# Power_suply.net
KiCad netlist of a schematic drawn in Altium Designer
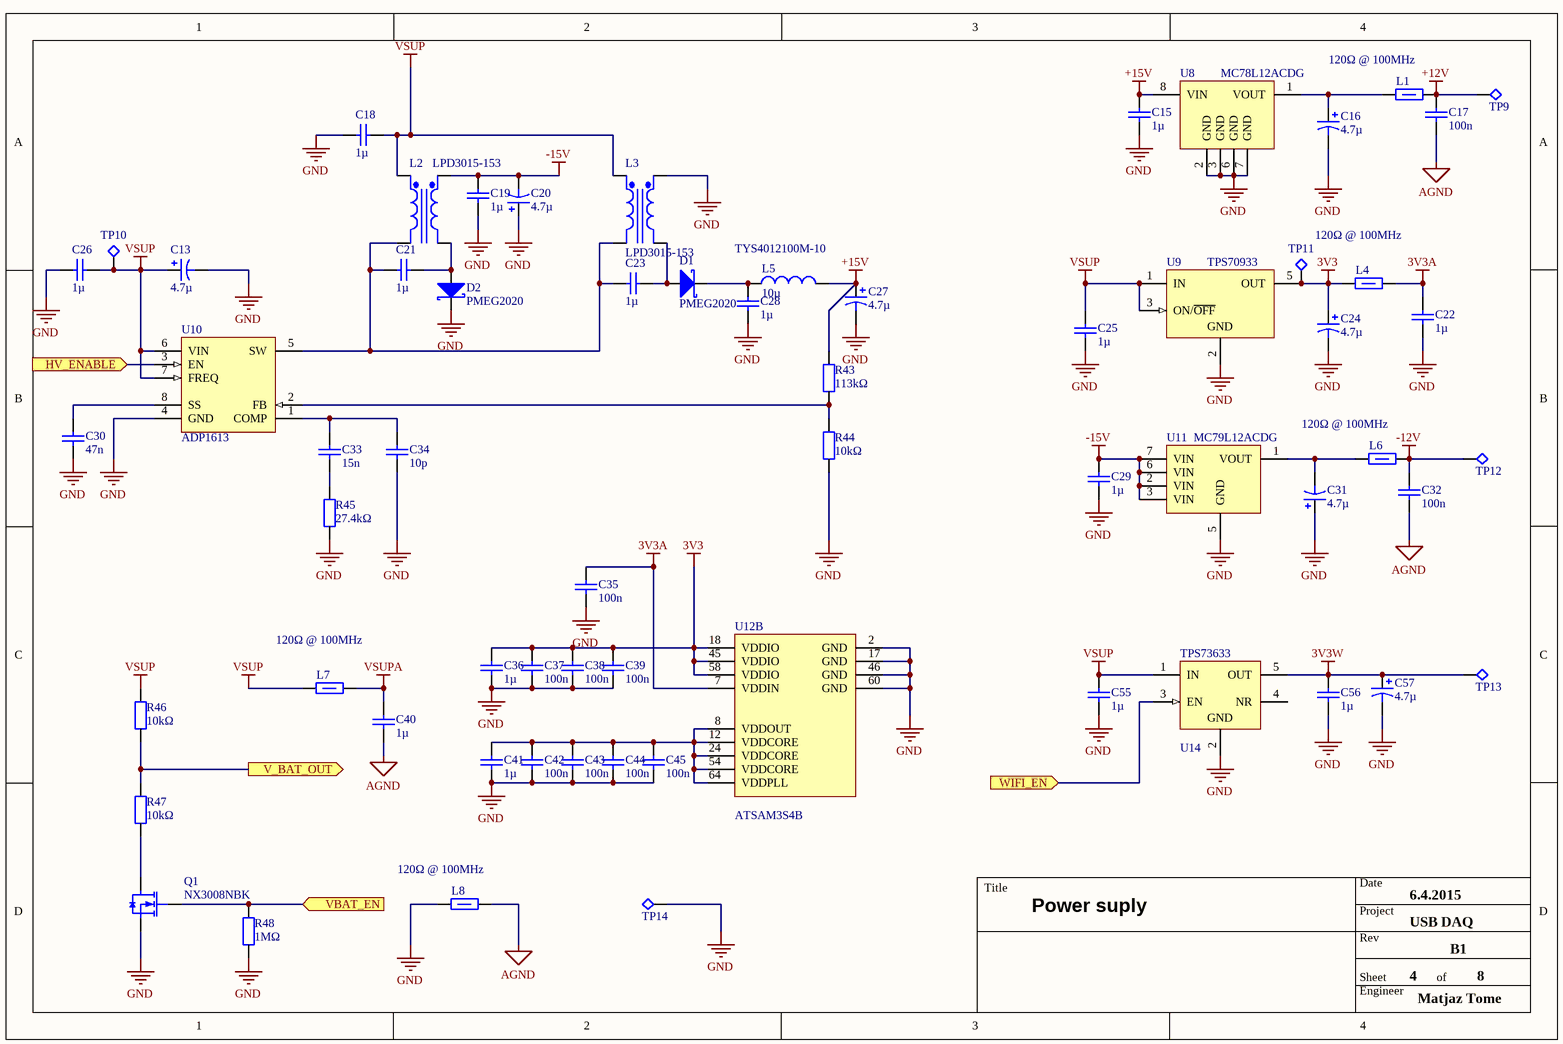
[diagram p0: Power_suply.SchDoc]

(export (version "E")
  (design (tool "Eeschema 10.0.6"))
  (components
    (comp (ref "C13")
      (value "4.7µ")
      (footprint "A")
      (description "tantalum SMD capacitor 4.7µF 16V A case")
      (fields (field (name "PART NUMBER") "CST0011") (field (name "MANUFACTURER") "Kemet"))
      (libsource (lib "components") (part "Capacitor polarized"))
    )
    (comp (ref "C15")
      (value "1µ")
      (footprint "0603C")
      (description "ceramic X5R SMD capacitor smd 0603 1µF 50V")
      (fields (field (name "PART NUMBER") "ZSC0003") (field (name "MANUFACTURER") "Murata"))
      (libsource (lib "components") (part "Capacitor"))
    )
    (comp (ref "C16")
      (value "4.7µ")
      (footprint "A")
      (description "tantalum SMD capacitor 4.7µF 16V A case")
      (fields (field (name "PART NUMBER") "CST0011") (field (name "MANUFACTURER") "Kemet"))
      (libsource (lib "components") (part "Capacitor polarized"))
    )
    (comp (ref "C17")
      (value "100n")
      (footprint "0603C")
      (description "ceramic X7R SMD capacitor smd 0603 100nF 16V")
      (fields (field (name "PART NUMBER") "RSC0013") (field (name "MANUFACTURER") "Murata"))
      (libsource (lib "components") (part "Capacitor"))
    )
    (comp (ref "C18")
      (value "1µ")
      (footprint "0603C")
      (description "ceramic X5R SMD capacitor smd 0603 1µF 50V")
      (fields (field (name "PART NUMBER") "ZSC0003") (field (name "MANUFACTURER") "Murata"))
      (libsource (lib "components") (part "Capacitor"))
    )
    (comp (ref "C19")
      (value "1µ")
      (footprint "0603C")
      (description "ceramic X5R SMD capacitor smd 0603 1µF 50V")
      (fields (field (name "PART NUMBER") "ZSC0003") (field (name "MANUFACTURER") "Murata"))
      (libsource (lib "components") (part "Capacitor"))
    )
    (comp (ref "C20")
      (value "4.7µ")
      (footprint "A")
      (description "tantalum SMD capacitor 4.7µF 16V A case")
      (fields (field (name "PART NUMBER") "CST0011") (field (name "MANUFACTURER") "Kemet"))
      (libsource (lib "components") (part "Capacitor polarized"))
    )
    (comp (ref "C21")
      (value "1µ")
      (footprint "0603C")
      (description "ceramic X5R SMD capacitor smd 0603 1µF 50V")
      (fields (field (name "PART NUMBER") "ZSC0003") (field (name "MANUFACTURER") "Murata"))
      (libsource (lib "components") (part "Capacitor"))
    )
    (comp (ref "C22")
      (value "1µ")
      (footprint "0603C")
      (description "ceramic X5R SMD capacitor smd 0603 1µF 50V")
      (fields (field (name "PART NUMBER") "ZSC0003") (field (name "MANUFACTURER") "Murata"))
      (libsource (lib "components") (part "Capacitor"))
    )
    (comp (ref "C23")
      (value "1µ")
      (footprint "0603C")
      (description "ceramic X5R SMD capacitor smd 0603 1µF 50V")
      (fields (field (name "PART NUMBER") "ZSC0003") (field (name "MANUFACTURER") "Murata"))
      (libsource (lib "components") (part "Capacitor"))
    )
    (comp (ref "C24")
      (value "4.7µ")
      (footprint "A")
      (description "tantalum SMD capacitor 4.7µF 16V A case")
      (fields (field (name "PART NUMBER") "CST0011") (field (name "MANUFACTURER") "Kemet"))
      (libsource (lib "components") (part "Capacitor polarized"))
    )
    (comp (ref "C25")
      (value "1µ")
      (footprint "0603C")
      (description "ceramic X5R SMD capacitor smd 0603 1µF 50V")
      (fields (field (name "PART NUMBER") "ZSC0003") (field (name "MANUFACTURER") "Murata"))
      (libsource (lib "components") (part "Capacitor"))
    )
    (comp (ref "C26")
      (value "1µ")
      (footprint "0603C")
      (description "ceramic X5R SMD capacitor smd 0603 1µF 50V")
      (fields (field (name "PART NUMBER") "ZSC0003") (field (name "MANUFACTURER") "Murata"))
      (libsource (lib "components") (part "Capacitor"))
    )
    (comp (ref "C27")
      (value "4.7µ")
      (footprint "A")
      (description "tantalum SMD capacitor 4.7µF 16V A case")
      (fields (field (name "PART NUMBER") "CST0011") (field (name "MANUFACTURER") "Kemet"))
      (libsource (lib "components") (part "Capacitor polarized"))
    )
    (comp (ref "C28")
      (value "1µ")
      (footprint "0603C")
      (description "ceramic X5R SMD capacitor smd 0603 1µF 50V")
      (fields (field (name "PART NUMBER") "ZSC0003") (field (name "MANUFACTURER") "Murata"))
      (libsource (lib "components") (part "Capacitor"))
    )
    (comp (ref "C29")
      (value "1µ")
      (footprint "0603C")
      (description "ceramic X5R SMD capacitor smd 0603 1µF 50V")
      (fields (field (name "PART NUMBER") "ZSC0003") (field (name "MANUFACTURER") "Murata"))
      (libsource (lib "components") (part "Capacitor"))
    )
    (comp (ref "C30")
      (value "47n")
      (footprint "0603C")
      (description "ceramic X7R SMD capacitor smd 0603 47nF 16V")
      (fields (field (name "PART NUMBER") "RSC0007") (field (name "MANUFACTURER") "Multicomp"))
      (libsource (lib "components") (part "Capacitor"))
    )
    (comp (ref "C31")
      (value "4.7µ")
      (footprint "A")
      (description "tantalum SMD capacitor 4.7µF 16V A case")
      (fields (field (name "PART NUMBER") "CST0011") (field (name "MANUFACTURER") "Kemet"))
      (libsource (lib "components") (part "Capacitor polarized"))
    )
    (comp (ref "C32")
      (value "100n")
      (footprint "0603C")
      (description "ceramic X7R SMD capacitor smd 0603 100nF 16V")
      (fields (field (name "PART NUMBER") "RSC0013") (field (name "MANUFACTURER") "Murata"))
      (libsource (lib "components") (part "Capacitor"))
    )
    (comp (ref "C33")
      (value "15n")
      (footprint "0603C")
      (description "ceramic X7R SMD capacitor smd 0603 15nF 100V")
      (fields (field (name "PART NUMBER") "RSC0015") (field (name "MANUFACTURER") "Kemet"))
      (libsource (lib "components") (part "Capacitor"))
    )
    (comp (ref "C34")
      (value "10p")
      (footprint "0603C")
      (description "ceramic C0G SMD capacitor smd 0603 10pF 100V")
      (fields (field (name "PART NUMBER") "GSC0019") (field (name "MANUFACTURER") "Kemet"))
      (libsource (lib "components") (part "Capacitor"))
    )
    (comp (ref "C35")
      (value "100n")
      (footprint "0603C")
      (description "ceramic X7R SMD capacitor smd 0603 100nF 16V")
      (fields (field (name "PART NUMBER") "RSC0013") (field (name "MANUFACTURER") "Murata"))
      (libsource (lib "components") (part "Capacitor"))
    )
    (comp (ref "C36")
      (value "1µ")
      (footprint "0603C")
      (description "ceramic X5R SMD capacitor smd 0603 1µF 50V")
      (fields (field (name "PART NUMBER") "ZSC0003") (field (name "MANUFACTURER") "Murata"))
      (libsource (lib "components") (part "Capacitor"))
    )
    (comp (ref "C37")
      (value "100n")
      (footprint "0603C")
      (description "ceramic X7R SMD capacitor smd 0603 100nF 16V")
      (fields (field (name "PART NUMBER") "RSC0013") (field (name "MANUFACTURER") "Murata"))
      (libsource (lib "components") (part "Capacitor"))
    )
    (comp (ref "C38")
      (value "100n")
      (footprint "0603C")
      (description "ceramic X7R SMD capacitor smd 0603 100nF 16V")
      (fields (field (name "PART NUMBER") "RSC0013") (field (name "MANUFACTURER") "Murata"))
      (libsource (lib "components") (part "Capacitor"))
    )
    (comp (ref "C39")
      (value "100n")
      (footprint "0603C")
      (description "ceramic X7R SMD capacitor smd 0603 100nF 16V")
      (fields (field (name "PART NUMBER") "RSC0013") (field (name "MANUFACTURER") "Murata"))
      (libsource (lib "components") (part "Capacitor"))
    )
    (comp (ref "C40")
      (value "1µ")
      (footprint "0603C")
      (description "ceramic X5R SMD capacitor smd 0603 1µF 50V")
      (fields (field (name "PART NUMBER") "ZSC0003") (field (name "MANUFACTURER") "Murata"))
      (libsource (lib "components") (part "Capacitor"))
    )
    (comp (ref "C41")
      (value "1µ")
      (footprint "0603C")
      (description "ceramic X5R SMD capacitor smd 0603 1µF 50V")
      (fields (field (name "PART NUMBER") "ZSC0003") (field (name "MANUFACTURER") "Murata"))
      (libsource (lib "components") (part "Capacitor"))
    )
    (comp (ref "C42")
      (value "100n")
      (footprint "0603C")
      (description "ceramic X7R SMD capacitor smd 0603 100nF 16V")
      (fields (field (name "PART NUMBER") "RSC0013") (field (name "MANUFACTURER") "Murata"))
      (libsource (lib "components") (part "Capacitor"))
    )
    (comp (ref "C43")
      (value "100n")
      (footprint "0603C")
      (description "ceramic X7R SMD capacitor smd 0603 100nF 16V")
      (fields (field (name "PART NUMBER") "RSC0013") (field (name "MANUFACTURER") "Murata"))
      (libsource (lib "components") (part "Capacitor"))
    )
    (comp (ref "C44")
      (value "100n")
      (footprint "0603C")
      (description "ceramic X7R SMD capacitor smd 0603 100nF 16V")
      (fields (field (name "PART NUMBER") "RSC0013") (field (name "MANUFACTURER") "Murata"))
      (libsource (lib "components") (part "Capacitor"))
    )
    (comp (ref "C45")
      (value "100n")
      (footprint "0603C")
      (description "ceramic X7R SMD capacitor smd 0603 100nF 16V")
      (fields (field (name "PART NUMBER") "RSC0013") (field (name "MANUFACTURER") "Murata"))
      (libsource (lib "components") (part "Capacitor"))
    )
    (comp (ref "C55")
      (value "1µ")
      (footprint "0603C")
      (description "ceramic X5R SMD capacitor smd 0603 1µF 50V")
      (fields (field (name "PART NUMBER") "ZSC0003") (field (name "MANUFACTURER") "Murata"))
      (libsource (lib "components") (part "Capacitor"))
    )
    (comp (ref "C56")
      (value "1µ")
      (footprint "0603C")
      (description "ceramic X5R SMD capacitor smd 0603 1µF 50V")
      (fields (field (name "PART NUMBER") "ZSC0003") (field (name "MANUFACTURER") "Murata"))
      (libsource (lib "components") (part "Capacitor"))
    )
    (comp (ref "C57")
      (value "4.7µ")
      (footprint "A")
      (description "tantalum SMD capacitor 4.7µF 16V A case")
      (fields (field (name "PART NUMBER") "CST0011") (field (name "MANUFACTURER") "Kemet"))
      (libsource (lib "components") (part "Capacitor polarized"))
    )
    (comp (ref "D1")
      (value "PMEG2020")
      (footprint "SOD323")
      (description "Shotkey diode 2A 20V")
      (fields (field (name "PART NUMBER") "XDS0004") (field (name "MANUFACTURER") "Infineon"))
      (libsource (lib "components") (part "SCHOTTKY1"))
    )
    (comp (ref "D2")
      (value "PMEG2020")
      (footprint "SOD323")
      (description "Shotkey diode 2A 20V")
      (fields (field (name "PART NUMBER") "XDS0004") (field (name "MANUFACTURER") "Infineon"))
      (libsource (lib "components") (part "SCHOTTKY1"))
    )
    (comp (ref "L1")
      (value "120Ω @ 100MHz")
      (footprint "0805R")
      (description "Ferrite bead, 0.15Ω, 200mA, 0805, 120E @ 100MHz")
      (fields (field (name "PART NUMBER") "XFB0000") (field (name "MANUFACTURER") "Murata"))
      (libsource (lib "components") (part "Ferrite Bead"))
    )
    (comp (ref "L2")
      (value "LPD3015-153")
      (footprint "LPD3015")
      (description "Coupled Inductors")
      (fields (field (name "PART NUMBER") "XCI0000") (field (name "MANUFACTURER") "Coilcraft"))
      (libsource (lib "components") (part "Inductor_coupled1"))
    )
    (comp (ref "L3")
      (value "LPD3015-153")
      (footprint "LPD3015")
      (description "Coupled Inductors")
      (fields (field (name "PART NUMBER") "XCI0000") (field (name "MANUFACTURER") "Coilcraft"))
      (libsource (lib "") (part "Inductor_coupled1_1"))
    )
    (comp (ref "L4")
      (value "120Ω @ 100MHz")
      (footprint "0805R")
      (description "Ferrite bead, 0.15Ω, 200mA, 0805, 120E @ 100MHz")
      (fields (field (name "PART NUMBER") "XFB0000") (field (name "MANUFACTURER") "Murata"))
      (libsource (lib "components") (part "Ferrite Bead"))
    )
    (comp (ref "L5")
      (value "10µ")
      (footprint "ind_4mmX4mm")
      (description "SMD inductor 10µH, 0.8A")
      (fields
        (field (name "PART NUMBER") "XXI0000")
        (field (name "MANUFACTURER") "Laird Technologies")
        (field (name "MANUFACTURER NUMBER") "TYS4012100M-10")
      )
      (libsource (lib "components") (part "Inductor"))
    )
    (comp (ref "L6")
      (value "120Ω @ 100MHz")
      (footprint "0805R")
      (description "Ferrite bead, 0.15Ω, 200mA, 0805, 120E @ 100MHz")
      (fields (field (name "PART NUMBER") "XFB0000") (field (name "MANUFACTURER") "Murata"))
      (libsource (lib "components") (part "Ferrite Bead"))
    )
    (comp (ref "L7")
      (value "120Ω @ 100MHz")
      (footprint "0805R")
      (description "Ferrite bead, 0.15Ω, 200mA, 0805, 120E @ 100MHz")
      (fields (field (name "PART NUMBER") "XFB0000") (field (name "MANUFACTURER") "Murata"))
      (libsource (lib "components") (part "Ferrite Bead"))
    )
    (comp (ref "L8")
      (value "120Ω @ 100MHz")
      (footprint "0805R")
      (description "Ferrite bead, 0.15Ω, 200mA, 0805, 120E @ 100MHz")
      (fields (field (name "PART NUMBER") "XFB0000") (field (name "MANUFACTURER") "Murata"))
      (libsource (lib "components") (part "Ferrite Bead"))
    )
    (comp (ref "Q1")
      (value "NX3008NBK")
      (footprint "SOT23-3")
      (description "30V 0.4A N-mosfet")
      (fields (field (name "PART NUMBER") "XMN0003") (field (name "MANUFACTURER") "NXP"))
      (libsource (lib "components") (part "MOSFET_2"))
    )
    (comp (ref "R43")
      (value "113kΩ")
      (footprint "0603R")
      (description "resistor smd 0603 113kΩ 1% 0.1w")
      (fields (field (name "PART NUMBER") "YRS0021") (field (name "MANUFACTURER") "Vishay"))
      (libsource (lib "components") (part "Resistor"))
    )
    (comp (ref "R44")
      (value "10kΩ")
      (footprint "0603R")
      (description "resistor smd 0603 10kΩ 1% 0.1w")
      (fields (field (name "PART NUMBER") "YRS0016") (field (name "MANUFACTURER") "Vishay"))
      (libsource (lib "components") (part "Resistor"))
    )
    (comp (ref "R45")
      (value "27.4kΩ")
      (footprint "0603R")
      (description "resistor smd 0603 27.4kΩ 1% 0.1w")
      (fields (field (name "PART NUMBER") "YRS0020") (field (name "MANUFACTURER") "Vishay"))
      (libsource (lib "components") (part "Resistor"))
    )
    (comp (ref "R46")
      (value "10kΩ")
      (footprint "0603R")
      (description "resistor smd 0603 10kΩ 1% 0.1w")
      (fields (field (name "PART NUMBER") "YRS0016") (field (name "MANUFACTURER") "Vishay"))
      (libsource (lib "components") (part "Resistor"))
    )
    (comp (ref "R47")
      (value "10kΩ")
      (footprint "0603R")
      (description "resistor smd 0603 10kΩ 1% 0.1w")
      (fields (field (name "PART NUMBER") "YRS0016") (field (name "MANUFACTURER") "Vishay"))
      (libsource (lib "components") (part "Resistor"))
    )
    (comp (ref "R48")
      (value "1MΩ")
      (footprint "0603R")
      (description "resistor smd 0603 1MΩ 5% 0.1w")
      (fields (field (name "PART NUMBER") "XRS0035") (field (name "MANUFACTURER") "Multicomp"))
      (libsource (lib "components") (part "Resistor"))
    )
    (comp (ref "TP9")
      (value "testpoint")
      (footprint "TP1_FULL")
      (description "testpoint 1.5mm diameter no hole")
      (fields (field (name "PART NUMBER") "XXC0006"))
      (libsource (lib "components") (part "Test Point"))
    )
    (comp (ref "TP10")
      (value "testpoint")
      (footprint "TP1_FULL")
      (description "testpoint 1.5mm diameter no hole")
      (fields (field (name "PART NUMBER") "XXC0006"))
      (libsource (lib "components") (part "Test Point"))
    )
    (comp (ref "TP11")
      (value "testpoint")
      (footprint "TP1_FULL")
      (description "testpoint 1.5mm diameter no hole")
      (fields (field (name "PART NUMBER") "XXC0006"))
      (libsource (lib "components") (part "Test Point"))
    )
    (comp (ref "TP12")
      (value "testpoint")
      (footprint "TP1_FULL")
      (description "testpoint 1.5mm diameter no hole")
      (fields (field (name "PART NUMBER") "XXC0006"))
      (libsource (lib "components") (part "Test Point"))
    )
    (comp (ref "TP13")
      (value "testpoint")
      (footprint "TP1_FULL")
      (description "testpoint 1.5mm diameter no hole")
      (fields (field (name "PART NUMBER") "XXC0006"))
      (libsource (lib "components") (part "Test Point"))
    )
    (comp (ref "TP14")
      (value "testpoint")
      (footprint "TP1_FULL")
      (description "testpoint 1.5mm diameter no hole")
      (fields (field (name "PART NUMBER") "XXC0006"))
      (libsource (lib "components") (part "Test Point"))
    )
    (comp (ref "U8")
      (value "MC78L12ACDG")
      (footprint "SOIC8")
      (description "100 mA Positive Voltage\r\nRegulator")
      (fields (field (name "PART NUMBER") "XLR0006") (field (name "MANUFACTURER") "ON Semiconductors"))
      (libsource (lib "components") (part "78LXX"))
    )
    (comp (ref "U9")
      (value "TPS70933")
      (footprint "SOT23-5")
      (description "1-µA IQ Voltage Regulators with Enable")
      (fields (field (name "PART NUMBER") "XLR0012") (field (name "MANUFACTURER") "Texas Instruments"))
      (libsource (lib "components") (part "TPS709XX"))
    )
    (comp (ref "U10")
      (value "ADP1613")
      (footprint "MSOP8")
      (fields (field (name "PART NUMBER") "XSW0008") (field (name "MANUFACTURER") "Analog devices"))
      (libsource (lib "components") (part "ADP161X"))
    )
    (comp (ref "U11")
      (value "MC79L12ACDG")
      (footprint "SOIC8")
      (description "100 mA Negative Voltage\r\nRegulator")
      (fields (field (name "PART NUMBER") "XLR0007") (field (name "MANUFACTURER") "ON Semiconductors"))
      (libsource (lib "components") (part "79LXX"))
    )
    (comp (ref "U12")
      (value "ATSAM3S4B")
      (footprint "LQFP64")
      (description "Cortex M3 ARM microcontroller")
      (fields (field (name "PART NUMBER") "XAM0003") (field (name "MANUFACTURER") "Atmel"))
      (libsource (lib "components") (part "ATSAM3SXB"))
    )
    (comp (ref "U14")
      (value "TPS73633")
      (footprint "SOT23-5")
      (description "Cap-Free, NMOS, 400-mA Low-Dropout Regulator with Reverse Current Protection")
      (fields (field (name "PART NUMBER") "XLR0013") (field (name "MANUFACTURER") "Texas instruments"))
      (libsource (lib "components") (part "TPS736_1"))
    )
  )
  (nets
    (net (code "1") (name "+12V") (class "Default")
      (node (ref "C17") (pin "1") (pinfunction "1_1") (pintype "passive"))
      (node (ref "L1") (pin "2") (pinfunction "2_2") (pintype "passive"))
      (node (ref "TP9") (pin "1") (pinfunction "1_1") (pintype "passive"))
    )
    (net (code "2") (name "+15V") (class "Default")
      (node (ref "C15") (pin "2") (pinfunction "2_2") (pintype "passive"))
      (node (ref "C27") (pin "1") (pinfunction "1_1") (pintype "passive"))
      (node (ref "L5") (pin "2") (pinfunction "2_2") (pintype "passive"))
      (node (ref "R43") (pin "2") (pinfunction "2_2") (pintype "passive"))
      (node (ref "U8") (pin "8") (pinfunction "VIN_8") (pintype "power_in"))
    )
    (net (code "3") (name "-12V") (class "Default")
      (node (ref "C32") (pin "1") (pinfunction "1_1") (pintype "passive"))
      (node (ref "L6") (pin "2") (pinfunction "2_2") (pintype "passive"))
      (node (ref "TP12") (pin "1") (pinfunction "1_1") (pintype "passive"))
    )
    (net (code "4") (name "-15V") (class "Default")
      (node (ref "C19") (pin "2") (pinfunction "2_2") (pintype "passive"))
      (node (ref "C20") (pin "2") (pinfunction "2_2") (pintype "passive"))
      (node (ref "C29") (pin "2") (pinfunction "2_2") (pintype "passive"))
      (node (ref "L2") (pin "1") (pinfunction "1_1") (pintype "passive"))
      (node (ref "U11") (pin "2") (pinfunction "VIN_2") (pintype "power_in"))
      (node (ref "U11") (pin "3") (pinfunction "VIN_3") (pintype "power_in"))
      (node (ref "U11") (pin "6") (pinfunction "VIN_6") (pintype "power_in"))
      (node (ref "U11") (pin "7") (pinfunction "VIN_7") (pintype "power_in"))
    )
    (net (code "5") (name "/HV_ENABLE") (class "Default")
      (node (ref "U10") (pin "3") (pinfunction "EN_3") (pintype "input"))
    )
    (net (code "6") (name "/VBAT_EN") (class "Default")
      (node (ref "Q1") (pin "1") (pinfunction "G_1") (pintype "passive"))
      (node (ref "R48") (pin "2") (pinfunction "2_2") (pintype "passive"))
    )
    (net (code "7") (name "/V_BAT_OUT") (class "Default")
      (node (ref "R46") (pin "1") (pinfunction "1_1") (pintype "passive"))
      (node (ref "R47") (pin "2") (pinfunction "2_2") (pintype "passive"))
    )
    (net (code "8") (name "/WIFI_EN") (class "Default")
      (node (ref "U14") (pin "3") (pinfunction "EN_3") (pintype "input"))
    )
    (net (code "9") (name "3V3") (class "Default")
      (node (ref "C24") (pin "1") (pinfunction "1_1") (pintype "passive"))
      (node (ref "C36") (pin "2") (pinfunction "2_2") (pintype "passive"))
      (node (ref "C37") (pin "1") (pinfunction "1_1") (pintype "passive"))
      (node (ref "C38") (pin "1") (pinfunction "1_1") (pintype "passive"))
      (node (ref "C39") (pin "1") (pinfunction "1_1") (pintype "passive"))
      (node (ref "L4") (pin "1") (pinfunction "1_1") (pintype "passive"))
      (node (ref "TP11") (pin "1") (pinfunction "1_1") (pintype "passive"))
      (node (ref "U12") (pin "18") (pinfunction "VDDIO_18") (pintype "power_in"))
      (node (ref "U12") (pin "45") (pinfunction "VDDIO_45") (pintype "power_in"))
      (node (ref "U12") (pin "58") (pinfunction "VDDIO_58") (pintype "power_in"))
      (node (ref "U9") (pin "5") (pinfunction "OUT_5") (pintype "power_in"))
    )
    (net (code "10") (name "3V3A") (class "Default")
      (node (ref "C22") (pin "2") (pinfunction "2_2") (pintype "passive"))
      (node (ref "C35") (pin "1") (pinfunction "1_1") (pintype "passive"))
      (node (ref "L4") (pin "2") (pinfunction "2_2") (pintype "passive"))
      (node (ref "U12") (pin "7") (pinfunction "VDDIN_7") (pintype "power_in"))
    )
    (net (code "11") (name "3V3W") (class "Default")
      (node (ref "C56") (pin "2") (pinfunction "2_2") (pintype "passive"))
      (node (ref "C57") (pin "1") (pinfunction "1_1") (pintype "passive"))
      (node (ref "TP13") (pin "1") (pinfunction "1_1") (pintype "passive"))
      (node (ref "U14") (pin "5") (pinfunction "OUT_5") (pintype "power_in"))
    )
    (net (code "12") (name "AGND") (class "Default")
      (node (ref "C17") (pin "2") (pinfunction "2_2") (pintype "passive"))
      (node (ref "C32") (pin "2") (pinfunction "2_2") (pintype "passive"))
      (node (ref "C40") (pin "1") (pinfunction "1_1") (pintype "passive"))
      (node (ref "L8") (pin "2") (pinfunction "2_2") (pintype "passive"))
    )
    (net (code "13") (name "GND") (class "Default")
      (node (ref "C13") (pin "2") (pinfunction "2_2") (pintype "passive"))
      (node (ref "C15") (pin "1") (pinfunction "1_1") (pintype "passive"))
      (node (ref "C16") (pin "2") (pinfunction "2_2") (pintype "passive"))
      (node (ref "C18") (pin "2") (pinfunction "2_2") (pintype "passive"))
      (node (ref "C19") (pin "1") (pinfunction "1_1") (pintype "passive"))
      (node (ref "C20") (pin "1") (pinfunction "1_1") (pintype "passive"))
      (node (ref "C22") (pin "1") (pinfunction "1_1") (pintype "passive"))
      (node (ref "C24") (pin "2") (pinfunction "2_2") (pintype "passive"))
      (node (ref "C25") (pin "1") (pinfunction "1_1") (pintype "passive"))
      (node (ref "C26") (pin "1") (pinfunction "1_1") (pintype "passive"))
      (node (ref "C27") (pin "2") (pinfunction "2_2") (pintype "passive"))
      (node (ref "C28") (pin "1") (pinfunction "1_1") (pintype "passive"))
      (node (ref "C29") (pin "1") (pinfunction "1_1") (pintype "passive"))
      (node (ref "C30") (pin "1") (pinfunction "1_1") (pintype "passive"))
      (node (ref "C31") (pin "1") (pinfunction "1_1") (pintype "passive"))
      (node (ref "C34") (pin "1") (pinfunction "1_1") (pintype "passive"))
      (node (ref "C35") (pin "2") (pinfunction "2_2") (pintype "passive"))
      (node (ref "C36") (pin "1") (pinfunction "1_1") (pintype "passive"))
      (node (ref "C37") (pin "2") (pinfunction "2_2") (pintype "passive"))
      (node (ref "C38") (pin "2") (pinfunction "2_2") (pintype "passive"))
      (node (ref "C39") (pin "2") (pinfunction "2_2") (pintype "passive"))
      (node (ref "C41") (pin "1") (pinfunction "1_1") (pintype "passive"))
      (node (ref "C42") (pin "2") (pinfunction "2_2") (pintype "passive"))
      (node (ref "C43") (pin "2") (pinfunction "2_2") (pintype "passive"))
      (node (ref "C44") (pin "2") (pinfunction "2_2") (pintype "passive"))
      (node (ref "C45") (pin "2") (pinfunction "2_2") (pintype "passive"))
      (node (ref "C55") (pin "1") (pinfunction "1_1") (pintype "passive"))
      (node (ref "C56") (pin "1") (pinfunction "1_1") (pintype "passive"))
      (node (ref "C57") (pin "2") (pinfunction "2_2") (pintype "passive"))
      (node (ref "D2") (pin "2") (pinfunction "K_2") (pintype "passive"))
      (node (ref "L3") (pin "4") (pinfunction "4_4") (pintype "passive"))
      (node (ref "L8") (pin "1") (pinfunction "1_1") (pintype "passive"))
      (node (ref "Q1") (pin "2") (pinfunction "S_2") (pintype "passive"))
      (node (ref "R44") (pin "1") (pinfunction "1_1") (pintype "passive"))
      (node (ref "R45") (pin "1") (pinfunction "1_1") (pintype "passive"))
      (node (ref "R48") (pin "1") (pinfunction "1_1") (pintype "passive"))
      (node (ref "TP14") (pin "1") (pinfunction "1_1") (pintype "passive"))
      (node (ref "U10") (pin "4") (pinfunction "GND_4") (pintype "power_in"))
      (node (ref "U11") (pin "5") (pinfunction "GND_5") (pintype "power_in"))
      (node (ref "U12") (pin "17") (pinfunction "GND_17") (pintype "power_in"))
      (node (ref "U12") (pin "2") (pinfunction "GND_2") (pintype "power_in"))
      (node (ref "U12") (pin "46") (pinfunction "GND_46") (pintype "power_in"))
      (node (ref "U12") (pin "60") (pinfunction "GND_60") (pintype "power_in"))
      (node (ref "U14") (pin "2") (pinfunction "GND_2") (pintype "power_in"))
      (node (ref "U8") (pin "2") (pinfunction "GND_2") (pintype "power_in"))
      (node (ref "U8") (pin "3") (pinfunction "GND_3") (pintype "power_in"))
      (node (ref "U8") (pin "6") (pinfunction "GND_6") (pintype "power_in"))
      (node (ref "U8") (pin "7") (pinfunction "GND_7") (pintype "power_in"))
      (node (ref "U9") (pin "2") (pinfunction "GND_2") (pintype "power_in"))
    )
    (net (code "14") (name "Net-(C33-Pad1)") (class "Default")
      (node (ref "C33") (pin "1") (pinfunction "1_1") (pintype "passive"))
      (node (ref "R45") (pin "2") (pinfunction "2_2") (pintype "passive"))
    )
    (net (code "15") (name "Net-(D1-A)") (class "Default")
      (node (ref "C23") (pin "1") (pinfunction "1_1") (pintype "passive"))
      (node (ref "D1") (pin "1") (pinfunction "A_1") (pintype "passive"))
      (node (ref "L3") (pin "3") (pinfunction "3_3") (pintype "passive"))
    )
    (net (code "16") (name "Net-(D1-K)") (class "Default")
      (node (ref "C28") (pin "2") (pinfunction "2_2") (pintype "passive"))
      (node (ref "D1") (pin "2") (pinfunction "K_2") (pintype "passive"))
      (node (ref "L5") (pin "1") (pinfunction "1_1") (pintype "passive"))
    )
    (net (code "17") (name "Net-(D2-A)") (class "Default")
      (node (ref "C21") (pin "1") (pinfunction "1_1") (pintype "passive"))
      (node (ref "D2") (pin "1") (pinfunction "A_1") (pintype "passive"))
      (node (ref "L2") (pin "2") (pinfunction "2_2") (pintype "passive"))
    )
    (net (code "18") (name "Net-(Q1-D)") (class "Default")
      (node (ref "Q1") (pin "3") (pinfunction "D_3") (pintype "passive"))
      (node (ref "R47") (pin "1") (pinfunction "1_1") (pintype "passive"))
    )
    (net (code "19") (name "Net-(U8-VOUT)") (class "Default")
      (node (ref "C16") (pin "1") (pinfunction "1_1") (pintype "passive"))
      (node (ref "L1") (pin "1") (pinfunction "1_1") (pintype "passive"))
      (node (ref "U8") (pin "1") (pinfunction "VOUT_1") (pintype "power_in"))
    )
    (net (code "20") (name "Net-(U10-COMP)") (class "Default")
      (node (ref "C33") (pin "2") (pinfunction "2_2") (pintype "passive"))
      (node (ref "C34") (pin "2") (pinfunction "2_2") (pintype "passive"))
      (node (ref "U10") (pin "1") (pinfunction "COMP_1") (pintype "passive"))
    )
    (net (code "21") (name "Net-(U10-FB)") (class "Default")
      (node (ref "R43") (pin "1") (pinfunction "1_1") (pintype "passive"))
      (node (ref "R44") (pin "2") (pinfunction "2_2") (pintype "passive"))
      (node (ref "U10") (pin "2") (pinfunction "FB_2") (pintype "input"))
    )
    (net (code "22") (name "Net-(U10-SS)") (class "Default")
      (node (ref "C30") (pin "2") (pinfunction "2_2") (pintype "passive"))
      (node (ref "U10") (pin "8") (pinfunction "SS_8") (pintype "passive"))
    )
    (net (code "23") (name "Net-(U10-SW)") (class "Default")
      (node (ref "C21") (pin "2") (pinfunction "2_2") (pintype "passive"))
      (node (ref "C23") (pin "2") (pinfunction "2_2") (pintype "passive"))
      (node (ref "L2") (pin "3") (pinfunction "3_3") (pintype "passive"))
      (node (ref "L3") (pin "2") (pinfunction "2_2") (pintype "passive"))
      (node (ref "U10") (pin "5") (pinfunction "SW_5") (pintype "passive"))
    )
    (net (code "24") (name "Net-(U11-VOUT)") (class "Default")
      (node (ref "C31") (pin "2") (pinfunction "2_2") (pintype "passive"))
      (node (ref "L6") (pin "1") (pinfunction "1_1") (pintype "passive"))
      (node (ref "U11") (pin "1") (pinfunction "VOUT_1") (pintype "power_in"))
    )
    (net (code "25") (name "Net-(U12B-VDDOUT)") (class "Default")
      (node (ref "C41") (pin "2") (pinfunction "2_2") (pintype "passive"))
      (node (ref "C42") (pin "1") (pinfunction "1_1") (pintype "passive"))
      (node (ref "C43") (pin "1") (pinfunction "1_1") (pintype "passive"))
      (node (ref "C44") (pin "1") (pinfunction "1_1") (pintype "passive"))
      (node (ref "C45") (pin "1") (pinfunction "1_1") (pintype "passive"))
      (node (ref "U12") (pin "12") (pinfunction "VDDCORE_12") (pintype "power_in"))
      (node (ref "U12") (pin "24") (pinfunction "VDDCORE_24") (pintype "power_in"))
      (node (ref "U12") (pin "54") (pinfunction "VDDCORE_54") (pintype "power_in"))
      (node (ref "U12") (pin "64") (pinfunction "VDDPLL_64") (pintype "power_in"))
      (node (ref "U12") (pin "8") (pinfunction "VDDOUT_8") (pintype "power_in"))
    )
    (net (code "26") (name "VSUP") (class "Default")
      (node (ref "C13") (pin "1") (pinfunction "1_1") (pintype "passive"))
      (node (ref "C18") (pin "1") (pinfunction "1_1") (pintype "passive"))
      (node (ref "C25") (pin "2") (pinfunction "2_2") (pintype "passive"))
      (node (ref "C26") (pin "2") (pinfunction "2_2") (pintype "passive"))
      (node (ref "C55") (pin "2") (pinfunction "2_2") (pintype "passive"))
      (node (ref "L2") (pin "4") (pinfunction "4_4") (pintype "passive"))
      (node (ref "L3") (pin "1") (pinfunction "1_1") (pintype "passive"))
      (node (ref "L7") (pin "1") (pinfunction "1_1") (pintype "passive"))
      (node (ref "R46") (pin "2") (pinfunction "2_2") (pintype "passive"))
      (node (ref "TP10") (pin "1") (pinfunction "1_1") (pintype "passive"))
      (node (ref "U10") (pin "6") (pinfunction "VIN_6") (pintype "power_in"))
      (node (ref "U10") (pin "7") (pinfunction "FREQ_7") (pintype "input"))
      (node (ref "U14") (pin "1") (pinfunction "IN_1") (pintype "power_in"))
      (node (ref "U9") (pin "1") (pinfunction "IN_1") (pintype "power_in"))
      (node (ref "U9") (pin "3") (pinfunction "ON/~{OFF}_3") (pintype "input"))
    )
    (net (code "27") (name "VSUPA") (class "Default")
      (node (ref "C40") (pin "2") (pinfunction "2_2") (pintype "passive"))
      (node (ref "L7") (pin "2") (pinfunction "2_2") (pintype "passive"))
    )
    (net (code "28") (name "unconnected-(U14-NR-Pad4)") (class "Default")
      (node (ref "U14") (pin "4") (pinfunction "NR_4") (pintype "passive"))
    )
  )
)
